# Microcontroller.net
KiCad netlist of a schematic drawn in Altium Designer
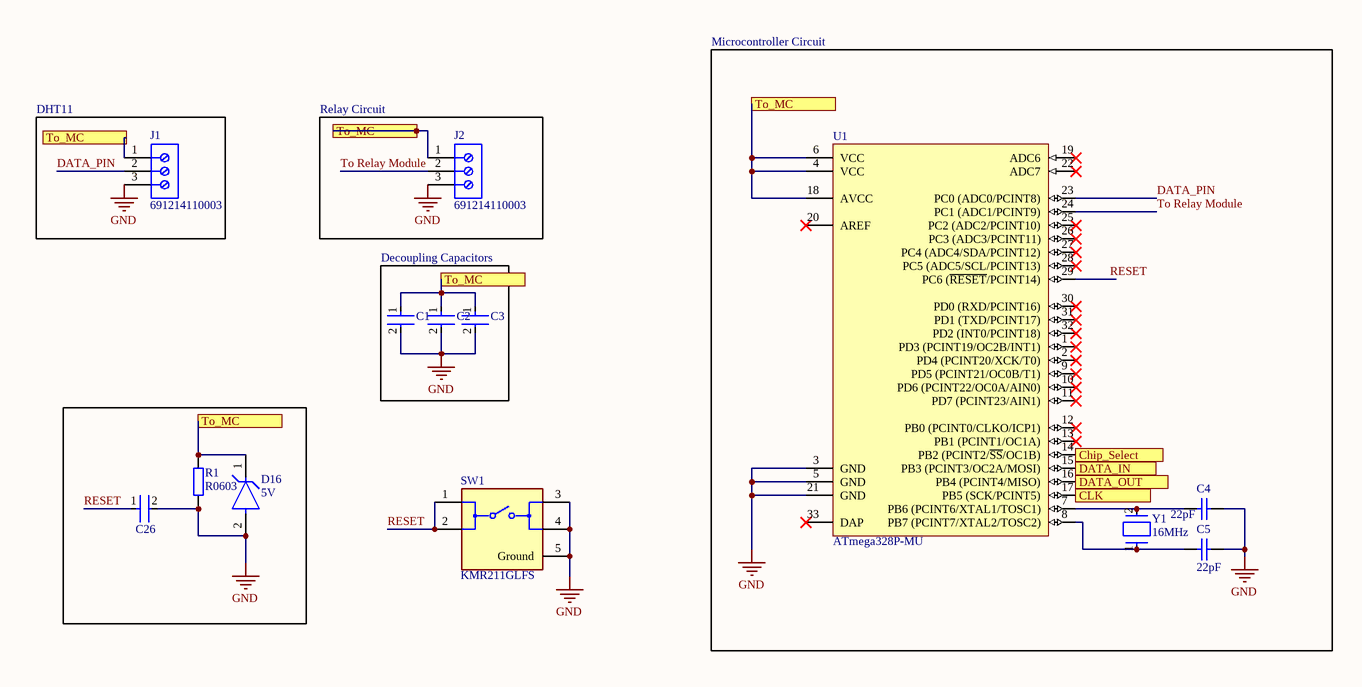
[diagram p0: Microcontroller.SchDoc, left]

(export (version "E")
  (design (tool "Eeschema 10.0.6"))
  (components
    (comp (ref "C1")
      (value "GRM033C71C104ME14D")
      (footprint "FP-GRM033-0_03-IPC_C")
      (description "Chip Multilayer Ceramic Capacitors for General Purpose, 0201, 0.10uF, X7S, 22%, 20%, 16V")
      (fields (field (name "TOLERANCE") "20%"))
      (libsource (lib "Altium Content Vault") (part "b4654b650e69147ec39a6b967a45e02"))
    )
    (comp (ref "C2")
      (value "GRM033C71C104ME14D")
      (footprint "FP-GRM033-0_03-IPC_C")
      (description "Chip Multilayer Ceramic Capacitors for General Purpose, 0201, 0.10uF, X7S, 22%, 20%, 16V")
      (fields (field (name "TOLERANCE") "20%"))
      (libsource (lib "Altium Content Vault") (part "b4654b650e69147ec39a6b967a45e02"))
    )
    (comp (ref "C3")
      (value "GRM033C71C104ME14D")
      (footprint "FP-GRM033-0_03-IPC_C")
      (description "Chip Multilayer Ceramic Capacitors for General Purpose, 0201, 0.10uF, X7S, 22%, 20%, 16V")
      (fields (field (name "TOLERANCE") "20%"))
      (libsource (lib "Altium Content Vault") (part "b4654b650e69147ec39a6b967a45e02"))
    )
    (comp (ref "C4")
      (value "22pF")
      (footprint "CAPC1608X90X35ML10T15")
      (description "Chip Capacitor, 22 pF, +/- 5%, 50 V, -55 to 125 degC, 0603 (1608 Metric), RoHS, Tape and Reel")
      (fields (field (name "MANUFACTURER") "Murata"))
      (libsource (lib "Altium Content Vault") (part "CAP-NP-2"))
    )
    (comp (ref "C5")
      (value "22pF")
      (footprint "CAPC1608X90X35ML10T15")
      (description "Chip Capacitor, 22 pF, +/- 5%, 50 V, -55 to 125 degC, 0603 (1608 Metric), RoHS, Tape and Reel")
      (fields (field (name "MANUFACTURER") "Murata"))
      (libsource (lib "Altium Content Vault") (part "CAP-NP-2"))
    )
    (comp (ref "C26")
      (value "GRM033C71C104ME14D")
      (footprint "FP-GRM033-0_03-IPC_C")
      (description "Chip Multilayer Ceramic Capacitors for General Purpose, 0201, 0.10uF, X7S, 22%, 20%, 16V")
      (fields (field (name "TOLERANCE") "20%"))
      (libsource (lib "Altium Content Vault") (part "b4654b650e69147ec39a6b967a45e02"))
    )
    (comp (ref "D16")
      (value "5V")
      (footprint "FP-SMA-MFG")
      (description "TVS DIODE 5V 9.2V SMA")
      (fields
        (field (name "MANUFACTURER") "Diodes Inc.")
        (field (name "MANUFACTURER PART NUMBER") "SMAJ5.0A-13-F")
      )
      (libsource (lib "Altium Content Vault") (part "f813f71cba58e380607f5dd3caf9714"))
    )
    (comp (ref "J1")
      (value "691214110003")
      (footprint "691214110003")
      (fields (field (name "VOLTAGE") "300V"))
      (libsource (lib "Altium Content Vault") (part "TBL - 1R - 03P - Screw"))
    )
    (comp (ref "J2")
      (value "691214110003")
      (footprint "691214110003")
      (fields (field (name "VOLTAGE") "300V"))
      (libsource (lib "Altium Content Vault") (part "TBL - 1R - 03P - Screw"))
    )
    (comp (ref "R1")
      (value "R0603")
      (footprint "RES_0603")
      (description "Resistor SMD 0603")
      (libsource (lib "PMS_LIB") (part "RES_0603"))
    )
    (comp (ref "SW1")
      (value "KMR211GLFS")
      (footprint "FP-KMR211GLFS-MFG")
      (description "SWITCH TACTILE SPST-NO 0.05A 32V")
      (libsource (lib "Altium Content Vault") (part "99988cc0f9d3d39bd794ae22da860e5"))
    )
    (comp (ref "U1")
      (value "ATmega328P-MU")
      (footprint "32M1-A_L")
      (libsource (lib "Altium Content Vault") (part "MC-8B-ATM48-SQ33"))
    )
    (comp (ref "Y1")
      (value "16MHz")
      (footprint "FP-ABM3-MFG")
      (description "Crystal 16MHz ±20ppm 18pF SMD-2 5mm x 3.2mm")
      (fields (field (name "TOLERANCE") "20ppm"))
      (libsource (lib "Altium Content Vault") (part "c23a69dc6c9e2f18f2079038eb95dd1"))
    )
  )
  (nets
    (net (code "1") (name "/CLK") (class "Default")
      (node (ref "U1") (pin "17") (pinfunction "PB5_(SCK/PCINT5)_17") (pintype "bidirectional"))
    )
    (net (code "2") (name "/Chip_Select") (class "Default")
      (node (ref "U1") (pin "14") (pinfunction "PB2_(PCINT2/~{SS}/OC1B)_14") (pintype "bidirectional"))
    )
    (net (code "3") (name "/DATA_IN") (class "Default")
      (node (ref "U1") (pin "15") (pinfunction "PB3_(PCINT3/OC2A/MOSI)_15") (pintype "bidirectional"))
    )
    (net (code "4") (name "/DATA_OUT") (class "Default")
      (node (ref "U1") (pin "16") (pinfunction "PB4_(PCINT4/MISO)_16") (pintype "bidirectional"))
    )
    (net (code "5") (name "/DATA_PIN") (class "Default")
      (node (ref "J1") (pin "2") (pinfunction "2_2") (pintype "passive"))
      (node (ref "U1") (pin "23") (pinfunction "PC0_(ADC0/PCINT8)_23") (pintype "bidirectional"))
    )
    (net (code "6") (name "/RESET") (class "Default")
      (node (ref "C26") (pin "1") (pinfunction "1_1") (pintype "passive"))
      (node (ref "SW1") (pin "1") (pinfunction "1_1") (pintype "passive"))
      (node (ref "SW1") (pin "2") (pinfunction "2_2") (pintype "passive"))
      (node (ref "U1") (pin "29") (pinfunction "PC6_(~{RESET}/PCINT14)_29") (pintype "bidirectional"))
    )
    (net (code "7") (name "/To Relay Module") (class "Default")
      (node (ref "J2") (pin "2") (pinfunction "2_2") (pintype "passive"))
      (node (ref "U1") (pin "24") (pinfunction "PC1_(ADC1/PCINT9)_24") (pintype "bidirectional"))
    )
    (net (code "8") (name "/To_MC") (class "Default")
      (node (ref "C1") (pin "1") (pinfunction "1_1") (pintype "passive"))
      (node (ref "C2") (pin "1") (pinfunction "1_1") (pintype "passive"))
      (node (ref "C3") (pin "1") (pinfunction "1_1") (pintype "passive"))
      (node (ref "D16") (pin "1") (pinfunction "C_1") (pintype "passive"))
      (node (ref "J1") (pin "1") (pinfunction "1_1") (pintype "passive"))
      (node (ref "J2") (pin "1") (pinfunction "1_1") (pintype "passive"))
      (node (ref "R1") (pin "2") (pinfunction "2_2") (pintype "passive"))
      (node (ref "U1") (pin "18") (pinfunction "AVCC_18") (pintype "power_in"))
      (node (ref "U1") (pin "4") (pinfunction "VCC_4") (pintype "power_in"))
      (node (ref "U1") (pin "6") (pinfunction "VCC_6") (pintype "power_in"))
    )
    (net (code "9") (name "GND") (class "Default")
      (node (ref "C1") (pin "2") (pinfunction "2_2") (pintype "passive"))
      (node (ref "C2") (pin "2") (pinfunction "2_2") (pintype "passive"))
      (node (ref "C26") (pin "2") (pinfunction "2_2") (pintype "passive"))
      (node (ref "C3") (pin "2") (pinfunction "2_2") (pintype "passive"))
      (node (ref "C4") (pin "2") (pinfunction "2_2") (pintype "passive"))
      (node (ref "C5") (pin "2") (pinfunction "2_2") (pintype "passive"))
      (node (ref "D16") (pin "2") (pinfunction "A_2") (pintype "passive"))
      (node (ref "J1") (pin "3") (pinfunction "3_3") (pintype "passive"))
      (node (ref "J2") (pin "3") (pinfunction "3_3") (pintype "passive"))
      (node (ref "R1") (pin "1") (pinfunction "1_1") (pintype "passive"))
      (node (ref "SW1") (pin "3") (pinfunction "3_3") (pintype "passive"))
      (node (ref "SW1") (pin "4") (pinfunction "4_4") (pintype "passive"))
      (node (ref "SW1") (pin "5") (pinfunction "Ground_5") (pintype "power_in"))
      (node (ref "U1") (pin "21") (pinfunction "GND_21") (pintype "power_in"))
      (node (ref "U1") (pin "3") (pinfunction "GND_3") (pintype "power_in"))
      (node (ref "U1") (pin "5") (pinfunction "GND_5") (pintype "power_in"))
    )
    (net (code "10") (name "Net-(U1-PB6_(PCINT6{slash}XTAL1{slash}TOSC1))") (class "Default")
      (node (ref "C4") (pin "1") (pinfunction "1_1") (pintype "passive"))
      (node (ref "U1") (pin "7") (pinfunction "PB6_(PCINT6/XTAL1/TOSC1)_7") (pintype "bidirectional"))
      (node (ref "Y1") (pin "2") (pinfunction "2_2") (pintype "passive"))
    )
    (net (code "11") (name "Net-(U1-PB7_(PCINT7{slash}XTAL2{slash}TOSC2))") (class "Default")
      (node (ref "C5") (pin "1") (pinfunction "1_1") (pintype "passive"))
      (node (ref "U1") (pin "8") (pinfunction "PB7_(PCINT7/XTAL2/TOSC2)_8") (pintype "bidirectional"))
      (node (ref "Y1") (pin "1") (pinfunction "1_1") (pintype "passive"))
    )
    (net (code "12") (name "unconnected-(U1-ADC6-Pad19)") (class "Default")
      (node (ref "U1") (pin "19") (pinfunction "ADC6_19") (pintype "input+no_connect"))
    )
    (net (code "13") (name "unconnected-(U1-ADC7-Pad22)") (class "Default")
      (node (ref "U1") (pin "22") (pinfunction "ADC7_22") (pintype "input+no_connect"))
    )
    (net (code "14") (name "unconnected-(U1-AREF-Pad20)") (class "Default")
      (node (ref "U1") (pin "20") (pinfunction "AREF_20") (pintype "passive+no_connect"))
    )
    (net (code "15") (name "unconnected-(U1-DAP-Pad33)") (class "Default")
      (node (ref "U1") (pin "33") (pinfunction "DAP_33") (pintype "power_in+no_connect"))
    )
    (net (code "16") (name "unconnected-(U1-PB0_(PCINT0{slash}CLKO{slash}ICP1)-Pad12)") (class "Default")
      (node (ref "U1") (pin "12") (pinfunction "PB0_(PCINT0/CLKO/ICP1)_12") (pintype "bidirectional+no_connect"))
    )
    (net (code "17") (name "unconnected-(U1-PB1_(PCINT1{slash}OC1A)-Pad13)") (class "Default")
      (node (ref "U1") (pin "13") (pinfunction "PB1_(PCINT1/OC1A)_13") (pintype "bidirectional+no_connect"))
    )
    (net (code "18") (name "unconnected-(U1-PC2_(ADC2{slash}PCINT10)-Pad25)") (class "Default")
      (node (ref "U1") (pin "25") (pinfunction "PC2_(ADC2/PCINT10)_25") (pintype "bidirectional+no_connect"))
    )
    (net (code "19") (name "unconnected-(U1-PC3_(ADC3{slash}PCINT11)-Pad26)") (class "Default")
      (node (ref "U1") (pin "26") (pinfunction "PC3_(ADC3/PCINT11)_26") (pintype "bidirectional+no_connect"))
    )
    (net (code "20") (name "unconnected-(U1-PC4_(ADC4{slash}SDA{slash}PCINT12)-Pad27)") (class "Default")
      (node (ref "U1") (pin "27") (pinfunction "PC4_(ADC4/SDA/PCINT12)_27") (pintype "bidirectional+no_connect"))
    )
    (net (code "21") (name "unconnected-(U1-PC5_(ADC5{slash}SCL{slash}PCINT13)-Pad28)") (class "Default")
      (node (ref "U1") (pin "28") (pinfunction "PC5_(ADC5/SCL/PCINT13)_28") (pintype "bidirectional+no_connect"))
    )
    (net (code "22") (name "unconnected-(U1-PD0_(RXD{slash}PCINT16)-Pad30)") (class "Default")
      (node (ref "U1") (pin "30") (pinfunction "PD0_(RXD/PCINT16)_30") (pintype "bidirectional+no_connect"))
    )
    (net (code "23") (name "unconnected-(U1-PD1_(TXD{slash}PCINT17)-Pad31)") (class "Default")
      (node (ref "U1") (pin "31") (pinfunction "PD1_(TXD/PCINT17)_31") (pintype "bidirectional+no_connect"))
    )
    (net (code "24") (name "unconnected-(U1-PD2_(INT0{slash}PCINT18)-Pad32)") (class "Default")
      (node (ref "U1") (pin "32") (pinfunction "PD2_(INT0/PCINT18)_32") (pintype "bidirectional+no_connect"))
    )
    (net (code "25") (name "unconnected-(U1-PD3_(PCINT19{slash}OC2B{slash}INT1)-Pad1)") (class "Default")
      (node (ref "U1") (pin "1") (pinfunction "PD3_(PCINT19/OC2B/INT1)_1") (pintype "bidirectional+no_connect"))
    )
    (net (code "26") (name "unconnected-(U1-PD4_(PCINT20{slash}XCK{slash}T0)-Pad2)") (class "Default")
      (node (ref "U1") (pin "2") (pinfunction "PD4_(PCINT20/XCK/T0)_2") (pintype "bidirectional+no_connect"))
    )
    (net (code "27") (name "unconnected-(U1-PD5_(PCINT21{slash}OC0B{slash}T1)-Pad9)") (class "Default")
      (node (ref "U1") (pin "9") (pinfunction "PD5_(PCINT21/OC0B/T1)_9") (pintype "bidirectional+no_connect"))
    )
    (net (code "28") (name "unconnected-(U1-PD6_(PCINT22{slash}OC0A{slash}AIN0)-Pad10)") (class "Default")
      (node (ref "U1") (pin "10") (pinfunction "PD6_(PCINT22/OC0A/AIN0)_10") (pintype "bidirectional+no_connect"))
    )
    (net (code "29") (name "unconnected-(U1-PD7_(PCINT23{slash}AIN1)-Pad11)") (class "Default")
      (node (ref "U1") (pin "11") (pinfunction "PD7_(PCINT23/AIN1)_11") (pintype "bidirectional+no_connect"))
    )
  )
)
